# programming.net
KiCad netlist of a schematic drawn in Altium Designer
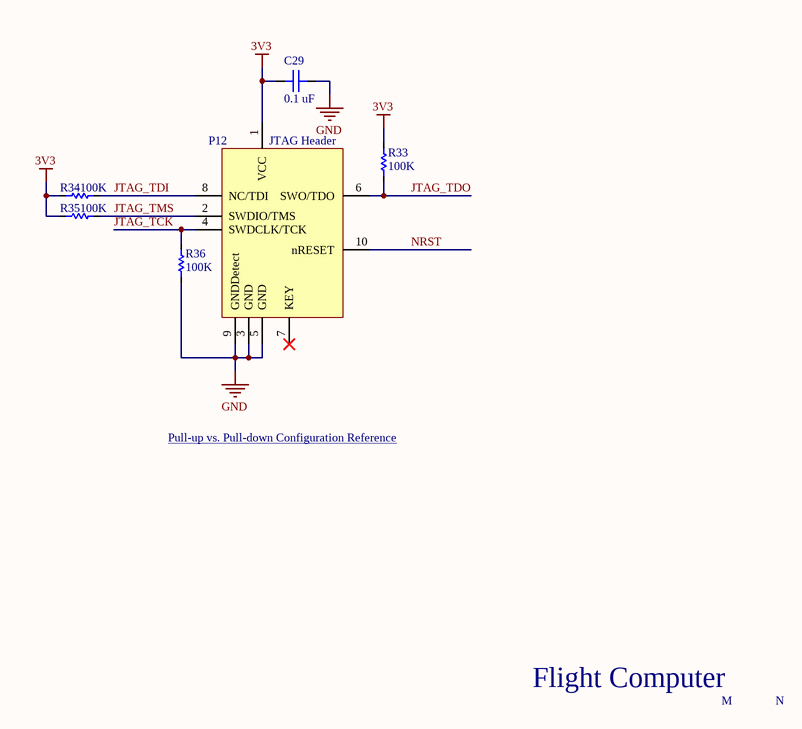
[diagram p0: programming.SchDoc]

(export (version "E")
  (design (tool "Eeschema 10.0.6"))
  (components
    (comp (ref "C29")
      (value "0.1 uF")
      (footprint "CAP-CER-0805-SHORT")
      (description "±10%, 0805")
      (libsource (lib "passive") (part "CAP-CER-0.1uF-25V"))
    )
    (comp (ref "P12")
      (value "JTAG Header")
      (footprint "SMD Header 5x2x1.27mm")
      (libsource (lib "connector") (part "10-pin JTAG Header"))
    )
    (comp (ref "R33")
      (value "100K")
      (footprint "RES-0805")
      (description "0805")
      (libsource (lib "passive") (part "RES-100K-1/8W"))
    )
    (comp (ref "R34")
      (value "100K")
      (footprint "RES-0805")
      (description "0805")
      (libsource (lib "passive") (part "RES-100K-1/8W"))
    )
    (comp (ref "R35")
      (value "100K")
      (footprint "RES-0805")
      (description "0805")
      (libsource (lib "passive") (part "RES-100K-1/8W"))
    )
    (comp (ref "R36")
      (value "100K")
      (footprint "RES-0805")
      (description "0805")
      (libsource (lib "passive") (part "RES-100K-1/8W"))
    )
  )
  (nets
    (net (code "1") (name "/JTAG_TCK") (class "Default")
      (node (ref "P12") (pin "4") (pinfunction "SWDCLK/TCK_4") (pintype "passive"))
      (node (ref "R36") (pin "2") (pinfunction "2_2") (pintype "passive"))
    )
    (net (code "2") (name "/JTAG_TDI") (class "Default")
      (node (ref "P12") (pin "8") (pinfunction "NC/TDI_8") (pintype "passive"))
      (node (ref "R34") (pin "1") (pinfunction "1_1") (pintype "passive"))
    )
    (net (code "3") (name "/JTAG_TDO") (class "Default")
      (node (ref "P12") (pin "6") (pinfunction "SWO/TDO_6") (pintype "passive"))
      (node (ref "R33") (pin "1") (pinfunction "1_1") (pintype "passive"))
    )
    (net (code "4") (name "/JTAG_TMS") (class "Default")
      (node (ref "P12") (pin "2") (pinfunction "SWDIO/TMS_2") (pintype "passive"))
      (node (ref "R35") (pin "1") (pinfunction "1_1") (pintype "passive"))
    )
    (net (code "5") (name "/NRST") (class "Default")
      (node (ref "P12") (pin "10") (pinfunction "nRESET_10") (pintype "passive"))
    )
    (net (code "6") (name "3V3") (class "Default")
      (node (ref "C29") (pin "1") (pinfunction "1_1") (pintype "passive"))
      (node (ref "P12") (pin "1") (pinfunction "VCC_1") (pintype "passive"))
      (node (ref "R33") (pin "2") (pinfunction "2_2") (pintype "passive"))
      (node (ref "R34") (pin "2") (pinfunction "2_2") (pintype "passive"))
      (node (ref "R35") (pin "2") (pinfunction "2_2") (pintype "passive"))
    )
    (net (code "7") (name "GND") (class "Default")
      (node (ref "C29") (pin "2") (pinfunction "2_2") (pintype "passive"))
      (node (ref "P12") (pin "3") (pinfunction "GND_3") (pintype "passive"))
      (node (ref "P12") (pin "5") (pinfunction "GND_5") (pintype "passive"))
      (node (ref "P12") (pin "9") (pinfunction "GNDDetect_9") (pintype "passive"))
      (node (ref "R36") (pin "1") (pinfunction "1_1") (pintype "passive"))
    )
    (net (code "8") (name "unconnected-(P12-KEY-Pad7)") (class "Default")
      (node (ref "P12") (pin "7") (pinfunction "KEY_7") (pintype "passive+no_connect"))
    )
  )
)
